# CANSplitter.net
KiCad netlist of a schematic drawn in EAGLE
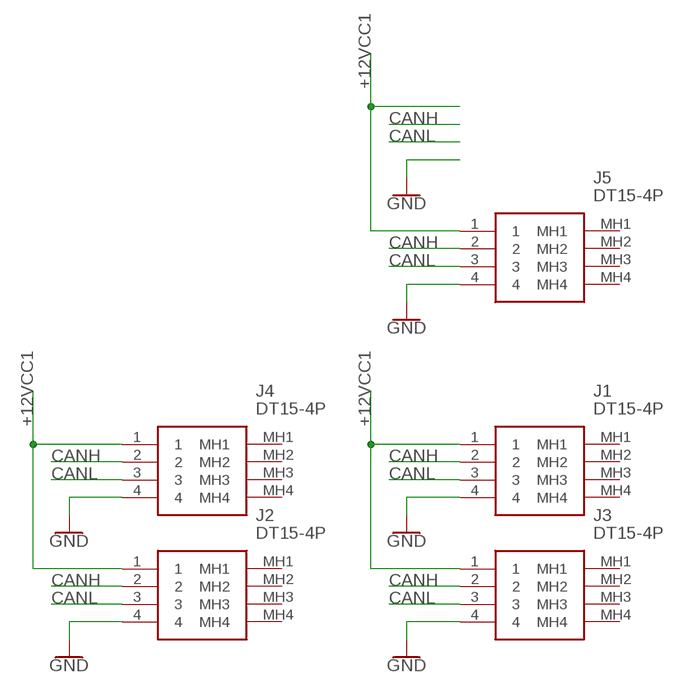
[diagram p0: schematic, sheet 1]

(export (version "E")
  (design (tool "Eeschema 10.0.6"))
  (components
    (comp (ref "J1")
      (value "DT15-4P")
      (footprint "eagle-import:DT154P")
      (fields (field (name "MOUSER_PART_NUMBER") "571-DT15-4P"))
      (libsource (lib "eagle-import") (part "DT15-4P"))
    )
    (comp (ref "J2")
      (value "DT15-4P")
      (footprint "eagle-import:DT154P")
      (fields (field (name "MOUSER_PART_NUMBER") "571-DT15-4P"))
      (libsource (lib "eagle-import") (part "DT15-4P"))
    )
    (comp (ref "J3")
      (value "DT15-4P")
      (footprint "eagle-import:DT154P")
      (fields (field (name "MOUSER_PART_NUMBER") "571-DT15-4P"))
      (libsource (lib "eagle-import") (part "DT15-4P"))
    )
    (comp (ref "J4")
      (value "DT15-4P")
      (footprint "eagle-import:DT154P")
      (fields (field (name "MOUSER_PART_NUMBER") "571-DT15-4P"))
      (libsource (lib "eagle-import") (part "DT15-4P"))
    )
    (comp (ref "J5")
      (value "DT15-4P")
      (footprint "eagle-import:DT154P")
      (fields (field (name "MOUSER_PART_NUMBER") "571-DT15-4P"))
      (libsource (lib "eagle-import") (part "DT15-4P"))
    )
  )
  (nets
    (net (code "1") (name "/+12VCC1") (class "Default")
      (node (ref "J1") (pin "1") (pinfunction "1_1") (pintype "bidirectional"))
      (node (ref "J2") (pin "1") (pinfunction "1_1") (pintype "bidirectional"))
      (node (ref "J3") (pin "1") (pinfunction "1_1") (pintype "bidirectional"))
      (node (ref "J4") (pin "1") (pinfunction "1_1") (pintype "bidirectional"))
      (node (ref "J5") (pin "1") (pinfunction "1_1") (pintype "bidirectional"))
    )
    (net (code "2") (name "/CANH") (class "Default")
      (node (ref "J1") (pin "2") (pinfunction "2_2") (pintype "bidirectional"))
      (node (ref "J2") (pin "2") (pinfunction "2_2") (pintype "bidirectional"))
      (node (ref "J3") (pin "2") (pinfunction "2_2") (pintype "bidirectional"))
      (node (ref "J4") (pin "2") (pinfunction "2_2") (pintype "bidirectional"))
      (node (ref "J5") (pin "2") (pinfunction "2_2") (pintype "bidirectional"))
    )
    (net (code "3") (name "/CANL") (class "Default")
      (node (ref "J1") (pin "3") (pinfunction "3_3") (pintype "bidirectional"))
      (node (ref "J2") (pin "3") (pinfunction "3_3") (pintype "bidirectional"))
      (node (ref "J3") (pin "3") (pinfunction "3_3") (pintype "bidirectional"))
      (node (ref "J4") (pin "3") (pinfunction "3_3") (pintype "bidirectional"))
      (node (ref "J5") (pin "3") (pinfunction "3_3") (pintype "bidirectional"))
    )
    (net (code "4") (name "GND") (class "Default")
      (node (ref "J1") (pin "4") (pinfunction "4_4") (pintype "bidirectional"))
      (node (ref "J2") (pin "4") (pinfunction "4_4") (pintype "bidirectional"))
      (node (ref "J3") (pin "4") (pinfunction "4_4") (pintype "bidirectional"))
      (node (ref "J4") (pin "4") (pinfunction "4_4") (pintype "bidirectional"))
      (node (ref "J5") (pin "4") (pinfunction "4_4") (pintype "bidirectional"))
    )
    (net (code "5") (name "unconnected-(J1-PadMH1)") (class "Default")
      (node (ref "J1") (pin "MH1") (pinfunction "MH1_MH1") (pintype "bidirectional"))
    )
    (net (code "6") (name "unconnected-(J1-PadMH2)") (class "Default")
      (node (ref "J1") (pin "MH2") (pinfunction "MH2_MH2") (pintype "bidirectional"))
    )
    (net (code "7") (name "unconnected-(J1-PadMH3)") (class "Default")
      (node (ref "J1") (pin "MH3") (pinfunction "MH3_MH3") (pintype "bidirectional"))
    )
    (net (code "8") (name "unconnected-(J1-PadMH4)") (class "Default")
      (node (ref "J1") (pin "MH4") (pinfunction "MH4_MH4") (pintype "bidirectional"))
    )
    (net (code "9") (name "unconnected-(J2-PadMH1)") (class "Default")
      (node (ref "J2") (pin "MH1") (pinfunction "MH1_MH1") (pintype "bidirectional"))
    )
    (net (code "10") (name "unconnected-(J2-PadMH2)") (class "Default")
      (node (ref "J2") (pin "MH2") (pinfunction "MH2_MH2") (pintype "bidirectional"))
    )
    (net (code "11") (name "unconnected-(J2-PadMH3)") (class "Default")
      (node (ref "J2") (pin "MH3") (pinfunction "MH3_MH3") (pintype "bidirectional"))
    )
    (net (code "12") (name "unconnected-(J2-PadMH4)") (class "Default")
      (node (ref "J2") (pin "MH4") (pinfunction "MH4_MH4") (pintype "bidirectional"))
    )
    (net (code "13") (name "unconnected-(J3-PadMH1)") (class "Default")
      (node (ref "J3") (pin "MH1") (pinfunction "MH1_MH1") (pintype "bidirectional"))
    )
    (net (code "14") (name "unconnected-(J3-PadMH2)") (class "Default")
      (node (ref "J3") (pin "MH2") (pinfunction "MH2_MH2") (pintype "bidirectional"))
    )
    (net (code "15") (name "unconnected-(J3-PadMH3)") (class "Default")
      (node (ref "J3") (pin "MH3") (pinfunction "MH3_MH3") (pintype "bidirectional"))
    )
    (net (code "16") (name "unconnected-(J3-PadMH4)") (class "Default")
      (node (ref "J3") (pin "MH4") (pinfunction "MH4_MH4") (pintype "bidirectional"))
    )
    (net (code "17") (name "unconnected-(J4-PadMH1)") (class "Default")
      (node (ref "J4") (pin "MH1") (pinfunction "MH1_MH1") (pintype "bidirectional"))
    )
    (net (code "18") (name "unconnected-(J4-PadMH2)") (class "Default")
      (node (ref "J4") (pin "MH2") (pinfunction "MH2_MH2") (pintype "bidirectional"))
    )
    (net (code "19") (name "unconnected-(J4-PadMH3)") (class "Default")
      (node (ref "J4") (pin "MH3") (pinfunction "MH3_MH3") (pintype "bidirectional"))
    )
    (net (code "20") (name "unconnected-(J4-PadMH4)") (class "Default")
      (node (ref "J4") (pin "MH4") (pinfunction "MH4_MH4") (pintype "bidirectional"))
    )
    (net (code "21") (name "unconnected-(J5-PadMH1)") (class "Default")
      (node (ref "J5") (pin "MH1") (pinfunction "MH1_MH1") (pintype "bidirectional"))
    )
    (net (code "22") (name "unconnected-(J5-PadMH2)") (class "Default")
      (node (ref "J5") (pin "MH2") (pinfunction "MH2_MH2") (pintype "bidirectional"))
    )
    (net (code "23") (name "unconnected-(J5-PadMH3)") (class "Default")
      (node (ref "J5") (pin "MH3") (pinfunction "MH3_MH3") (pintype "bidirectional"))
    )
    (net (code "24") (name "unconnected-(J5-PadMH4)") (class "Default")
      (node (ref "J5") (pin "MH4") (pinfunction "MH4_MH4") (pintype "bidirectional"))
    )
  )
)
